# TapuinoMini.net
KiCad netlist of a schematic drawn in EAGLE
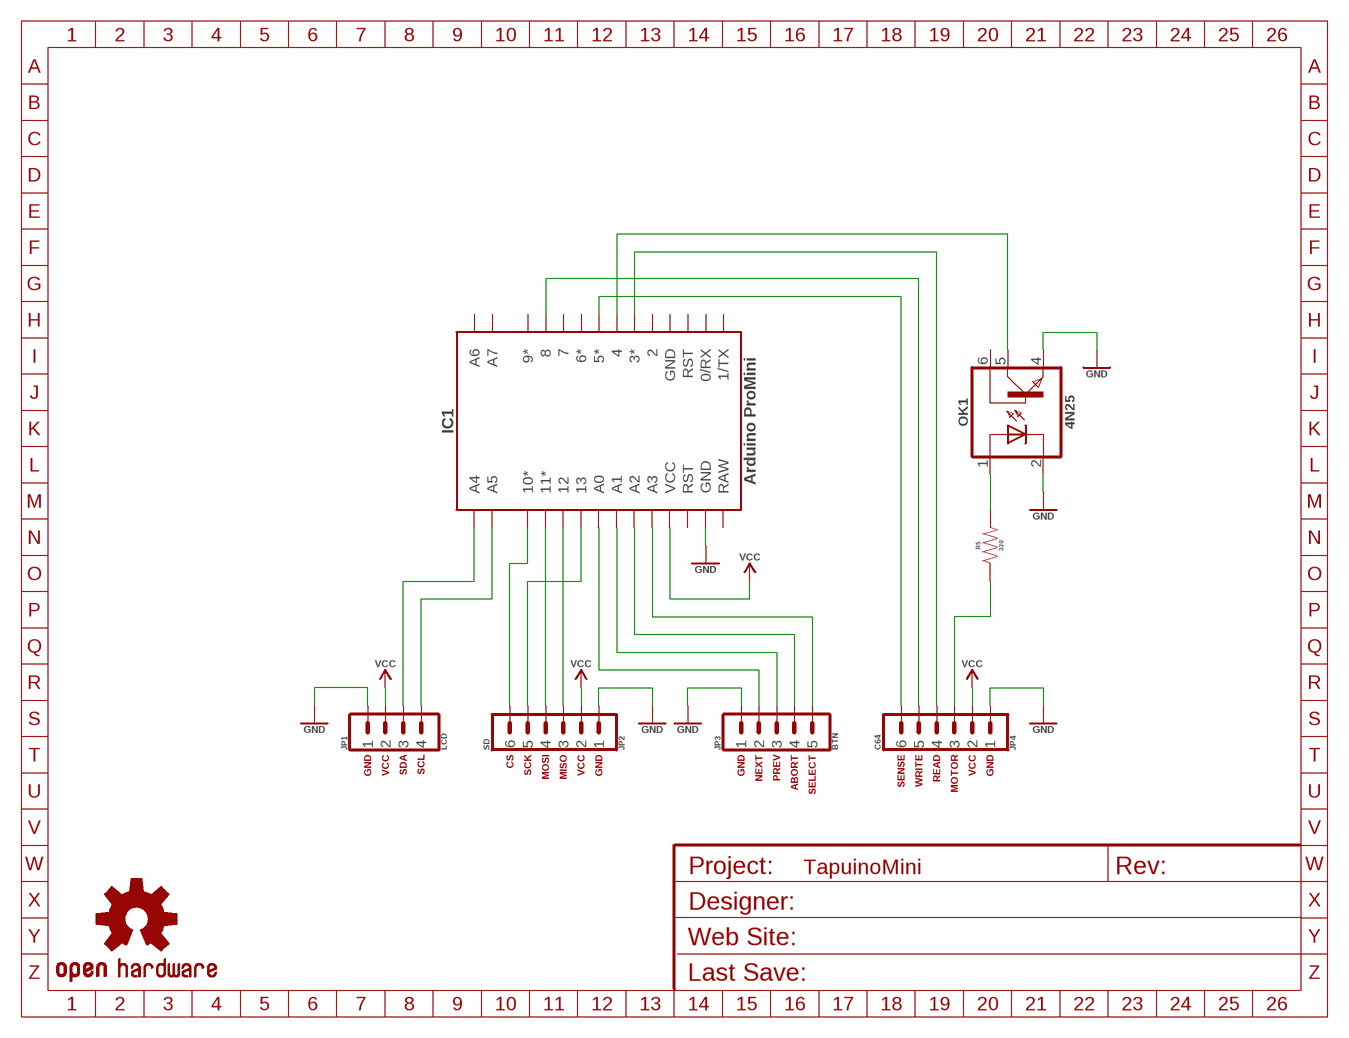
[diagram p0: schematic, sheet 1]

(export (version "E")
  (design (tool "Eeschema 10.0.6"))
  (components
    (comp (ref "IC1")
      (value "Arduino ProMini")
      (footprint "eagle-import:PROMINI_A")
      (libsource (lib "eagle-import") (part "PROMINI_A"))
    )
    (comp (ref "JP1")
      (value "LCD")
      (footprint "eagle-import:1X04_SQR")
      (libsource (lib "eagle-import") (part "1X04_SQR"))
    )
    (comp (ref "JP2")
      (value "SD")
      (footprint "eagle-import:1X06_SQR")
      (libsource (lib "eagle-import") (part "1X06_SQR"))
    )
    (comp (ref "JP3")
      (value "BTN")
      (footprint "eagle-import:1X05_SQR")
      (libsource (lib "eagle-import") (part "1X05_SQR"))
    )
    (comp (ref "JP4")
      (value "C64")
      (footprint "eagle-import:1X06_SQR")
      (libsource (lib "eagle-import") (part "1X06_SQR"))
    )
    (comp (ref "LOGO1")
      (value "OSHW_LOGO_SMALL")
      (footprint "eagle-import:OSHW_LOGO_SMALL")
      (libsource (lib "eagle-import") (part "OSHW_LOGO_SMALL"))
    )
    (comp (ref "OK1")
      (value "4N25")
      (footprint "eagle-import:DIP06")
      (libsource (lib "eagle-import") (part "OPTO_6PIN_4NXX"))
    )
    (comp (ref "R5")
      (value "330")
      (footprint "eagle-import:RESISTOR_PTH_0.3")
      (libsource (lib "eagle-import") (part "RESISTOR_PTH_0.3"))
    )
  )
  (nets
    (net (code "1") (name "GND") (class "Default")
      (node (ref "IC1") (pin "GND@1") (pinfunction "GND_GND@1") (pintype "bidirectional"))
      (node (ref "JP1") (pin "1") (pinfunction "1_1") (pintype "passive"))
      (node (ref "JP2") (pin "1") (pinfunction "1_1") (pintype "passive"))
      (node (ref "JP3") (pin "1") (pinfunction "1_1") (pintype "passive"))
      (node (ref "JP4") (pin "1") (pinfunction "1_1") (pintype "passive"))
      (node (ref "OK1") (pin "2") (pinfunction "CATHODE_2") (pintype "passive"))
      (node (ref "OK1") (pin "4") (pinfunction "EMITTER_4") (pintype "passive"))
    )
    (net (code "2") (name "Net-(IC1-Pad3*)") (class "Default")
      (node (ref "IC1") (pin "3*") (pinfunction "3*_3*") (pintype "bidirectional"))
      (node (ref "JP4") (pin "4") (pinfunction "4_4") (pintype "passive"))
    )
    (net (code "3") (name "Net-(IC1-Pad5*)") (class "Default")
      (node (ref "IC1") (pin "5*") (pinfunction "5*_5*") (pintype "bidirectional"))
      (node (ref "JP4") (pin "6") (pinfunction "6_6") (pintype "passive"))
    )
    (net (code "4") (name "Net-(IC1-Pad8)") (class "Default")
      (node (ref "IC1") (pin "8") (pinfunction "8_8") (pintype "bidirectional"))
      (node (ref "JP4") (pin "5") (pinfunction "5_5") (pintype "passive"))
    )
    (net (code "5") (name "Net-(IC1-Pad10*)") (class "Default")
      (node (ref "IC1") (pin "10*") (pinfunction "10*_10*") (pintype "bidirectional"))
      (node (ref "JP2") (pin "6") (pinfunction "6_6") (pintype "passive"))
    )
    (net (code "6") (name "Net-(IC1-Pad11*)") (class "Default")
      (node (ref "IC1") (pin "11*") (pinfunction "11*_11*") (pintype "bidirectional"))
      (node (ref "JP2") (pin "4") (pinfunction "4_4") (pintype "passive"))
    )
    (net (code "7") (name "Net-(IC1-Pad12)") (class "Default")
      (node (ref "IC1") (pin "12") (pinfunction "12_12") (pintype "bidirectional"))
      (node (ref "JP2") (pin "3") (pinfunction "3_3") (pintype "passive"))
    )
    (net (code "8") (name "Net-(IC1-Pad13)") (class "Default")
      (node (ref "IC1") (pin "13") (pinfunction "13_13") (pintype "bidirectional"))
      (node (ref "JP2") (pin "5") (pinfunction "5_5") (pintype "passive"))
    )
    (net (code "9") (name "Net-(IC1-PadA0)") (class "Default")
      (node (ref "IC1") (pin "A0") (pinfunction "A0_A0") (pintype "bidirectional"))
      (node (ref "JP3") (pin "2") (pinfunction "2_2") (pintype "passive"))
    )
    (net (code "10") (name "Net-(IC1-PadA1)") (class "Default")
      (node (ref "IC1") (pin "A1") (pinfunction "A1_A1") (pintype "bidirectional"))
      (node (ref "JP3") (pin "3") (pinfunction "3_3") (pintype "passive"))
    )
    (net (code "11") (name "Net-(IC1-PadA2)") (class "Default")
      (node (ref "IC1") (pin "A2") (pinfunction "A2_A2") (pintype "bidirectional"))
      (node (ref "JP3") (pin "4") (pinfunction "4_4") (pintype "passive"))
    )
    (net (code "12") (name "Net-(IC1-PadA3)") (class "Default")
      (node (ref "IC1") (pin "A3") (pinfunction "A3_A3") (pintype "bidirectional"))
      (node (ref "JP3") (pin "5") (pinfunction "5_5") (pintype "passive"))
    )
    (net (code "13") (name "Net-(IC1-PadA4)") (class "Default")
      (node (ref "IC1") (pin "A4") (pinfunction "A4_A4") (pintype "bidirectional"))
      (node (ref "JP1") (pin "3") (pinfunction "3_3") (pintype "passive"))
    )
    (net (code "14") (name "Net-(IC1-PadA5)") (class "Default")
      (node (ref "IC1") (pin "A5") (pinfunction "A5_A5") (pintype "bidirectional"))
      (node (ref "JP1") (pin "4") (pinfunction "4_4") (pintype "passive"))
    )
    (net (code "15") (name "Net-(JP4-Pad3)") (class "Default")
      (node (ref "JP4") (pin "3") (pinfunction "3_3") (pintype "passive"))
      (node (ref "R5") (pin "1") (pinfunction "1_1") (pintype "passive"))
    )
    (net (code "16") (name "Net-(OK1-ANODE)") (class "Default")
      (node (ref "OK1") (pin "1") (pinfunction "ANODE_1") (pintype "passive"))
      (node (ref "R5") (pin "2") (pinfunction "2_2") (pintype "passive"))
    )
    (net (code "17") (name "Net-(OK1-COLLECTOR)") (class "Default")
      (node (ref "IC1") (pin "4") (pinfunction "4_4") (pintype "bidirectional"))
      (node (ref "OK1") (pin "5") (pinfunction "COLLECTOR_5") (pintype "passive"))
    )
    (net (code "18") (name "VCC") (class "Default")
      (node (ref "IC1") (pin "VCC") (pinfunction "VCC_VCC") (pintype "bidirectional"))
      (node (ref "JP1") (pin "2") (pinfunction "2_2") (pintype "passive"))
      (node (ref "JP2") (pin "2") (pinfunction "2_2") (pintype "passive"))
      (node (ref "JP4") (pin "2") (pinfunction "2_2") (pintype "passive"))
    )
    (net (code "19") (name "unconnected-(IC1-GND-PadGND@2)") (class "Default")
      (node (ref "IC1") (pin "GND@2") (pinfunction "GND_GND@2") (pintype "bidirectional"))
    )
    (net (code "20") (name "unconnected-(IC1-Pad0{slash}RX)") (class "Default")
      (node (ref "IC1") (pin "0/RX") (pinfunction "0/RX_0/RX") (pintype "bidirectional"))
    )
    (net (code "21") (name "unconnected-(IC1-Pad1{slash}TX)") (class "Default")
      (node (ref "IC1") (pin "1/TX") (pinfunction "1/TX_1/TX") (pintype "bidirectional"))
    )
    (net (code "22") (name "unconnected-(IC1-Pad2)") (class "Default")
      (node (ref "IC1") (pin "2") (pinfunction "2_2") (pintype "bidirectional"))
    )
    (net (code "23") (name "unconnected-(IC1-Pad6*)") (class "Default")
      (node (ref "IC1") (pin "6*") (pinfunction "6*_6*") (pintype "bidirectional"))
    )
    (net (code "24") (name "unconnected-(IC1-Pad7)") (class "Default")
      (node (ref "IC1") (pin "7") (pinfunction "7_7") (pintype "bidirectional"))
    )
    (net (code "25") (name "unconnected-(IC1-Pad9*)") (class "Default")
      (node (ref "IC1") (pin "9*") (pinfunction "9*_9*") (pintype "bidirectional"))
    )
    (net (code "26") (name "unconnected-(IC1-PadA6)") (class "Default")
      (node (ref "IC1") (pin "A6") (pinfunction "A6_A6") (pintype "bidirectional"))
    )
    (net (code "27") (name "unconnected-(IC1-PadA7)") (class "Default")
      (node (ref "IC1") (pin "A7") (pinfunction "A7_A7") (pintype "bidirectional"))
    )
    (net (code "28") (name "unconnected-(IC1-PadRAW)") (class "Default")
      (node (ref "IC1") (pin "RAW") (pinfunction "RAW_RAW") (pintype "bidirectional"))
    )
    (net (code "29") (name "unconnected-(IC1-RST-PadRST@1)") (class "Default")
      (node (ref "IC1") (pin "RST@1") (pinfunction "RST_RST@1") (pintype "bidirectional"))
    )
    (net (code "30") (name "unconnected-(IC1-RST-PadRST@2)") (class "Default")
      (node (ref "IC1") (pin "RST@2") (pinfunction "RST_RST@2") (pintype "bidirectional"))
    )
    (net (code "31") (name "unconnected-(OK1-BASE-Pad6)") (class "Default")
      (node (ref "OK1") (pin "6") (pinfunction "BASE_6") (pintype "passive"))
    )
  )
)
